# Sheet3.net
KiCad netlist of a schematic drawn in Altium Designer
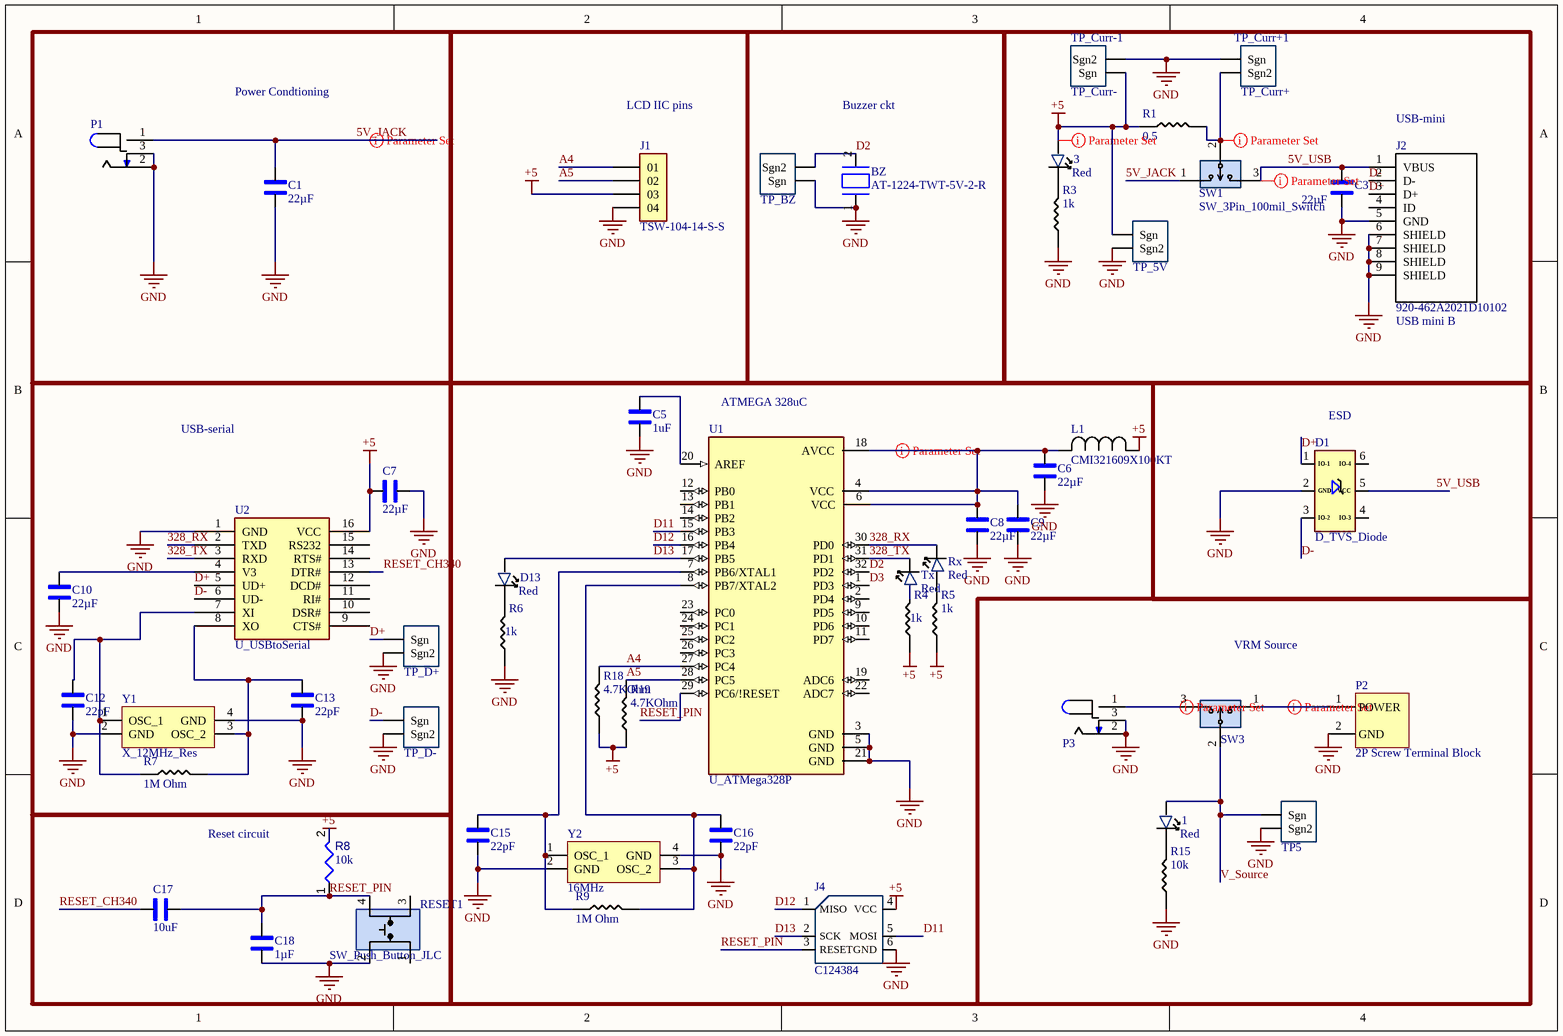
[diagram p0: Sheet3.SchDoc]

(export (version "E")
  (design (tool "Eeschema 10.0.6"))
  (components
    (comp (ref "1")
      (value "Red")
      (footprint "LED_1206")
      (description "Red 621~631nm 1206 Light Emitting Diodes (LED) RoHS")
      (fields (field (name "LCSC PART#") "C93133") (field (name "MFR PART #") "15-21/R6C-FQ1R1B/2T"))
      (libsource (lib "University of Colorado") (part "LED_YELLOW_1206"))
    )
    (comp (ref "3")
      (value "Red")
      (footprint "LED_1206")
      (description "Red 621~631nm 1206 Light Emitting Diodes (LED) RoHS")
      (fields (field (name "LCSC PART#") "C93133") (field (name "MFR PART #") "15-21/R6C-FQ1R1B/2T"))
      (libsource (lib "University of Colorado") (part "LED_YELLOW_1206"))
    )
    (comp (ref "BZ")
      (value "AT-1224-TWT-5V-2-R")
      (footprint "BUZZER- TH")
      (fields (field (name "MFR PART #") "AT-1224-TWT-5V-2-R"))
      (libsource (lib "ECEN5730Lib_2023_05_DS") (part "BUZZER_1"))
    )
    (comp (ref "C1")
      (value "22µF")
      (footprint "1206_Passive_Capacitor")
      (description "22uF ±10% 25V X5R 1206 Multilayer Ceramic Capacitors MLCC - SMD/SMT RoHS")
      (fields (field (name "LCSC PART#") "C12891") (field (name "MFR PART #") "CL31A226KAHNNNE"))
      (libsource (lib "University of Colorado") (part "C_47nF_1206"))
    )
    (comp (ref "C3")
      (value "22µF")
      (footprint "1206_Passive_Capacitor")
      (description "22uF ±10% 25V X5R 1206 Multilayer Ceramic Capacitors MLCC - SMD/SMT RoHS")
      (fields (field (name "LCSC PART#") "C12891") (field (name "MFR PART #") "CL31A226KAHNNNE"))
      (libsource (lib "University of Colorado") (part "C_47nF_1206"))
    )
    (comp (ref "C5")
      (value "1uF")
      (footprint "1206_Passive_Capacitor")
      (description "MULTILAYER CERAMIC CAPACITORS MLCC - SMD/SMT 1UF 50V 1206 ROHS")
      (fields (field (name "MFR PART #") "CL31B105KBHNNNE") (field (name "LCSC PART#") "C1848"))
      (libsource (lib "ECEN5730Lib_2023_05_DS") (part "C_1uF_1206"))
    )
    (comp (ref "C6")
      (value "22µF")
      (footprint "1206_Passive_Capacitor")
      (description "22uF ±10% 25V X5R 1206 Multilayer Ceramic Capacitors MLCC - SMD/SMT RoHS")
      (fields (field (name "LCSC PART#") "C12891") (field (name "MFR PART #") "CL31A226KAHNNNE"))
      (libsource (lib "University of Colorado") (part "C_47nF_1206"))
    )
    (comp (ref "C7")
      (value "22µF")
      (footprint "1206_Passive_Capacitor")
      (description "22uF ±10% 25V X5R 1206 Multilayer Ceramic Capacitors MLCC - SMD/SMT RoHS")
      (fields (field (name "LCSC PART#") "C12891") (field (name "MFR PART #") "CL31A226KAHNNNE"))
      (libsource (lib "University of Colorado") (part "C_47nF_1206"))
    )
    (comp (ref "C8")
      (value "22µF")
      (footprint "1206_Passive_Capacitor")
      (description "22uF ±10% 25V X5R 1206 Multilayer Ceramic Capacitors MLCC - SMD/SMT RoHS")
      (fields (field (name "LCSC PART#") "C12891") (field (name "MFR PART #") "CL31A226KAHNNNE"))
      (libsource (lib "University of Colorado") (part "C_47nF_1206"))
    )
    (comp (ref "C9")
      (value "22µF")
      (footprint "1206_Passive_Capacitor")
      (description "22uF ±10% 25V X5R 1206 Multilayer Ceramic Capacitors MLCC - SMD/SMT RoHS")
      (fields (field (name "LCSC PART#") "C12891") (field (name "MFR PART #") "CL31A226KAHNNNE"))
      (libsource (lib "University of Colorado") (part "C_47nF_1206"))
    )
    (comp (ref "C10")
      (value "22µF")
      (footprint "1206_Passive_Capacitor")
      (description "22uF ±10% 25V X5R 1206 Multilayer Ceramic Capacitors MLCC - SMD/SMT RoHS")
      (fields (field (name "LCSC PART#") "C12891") (field (name "MFR PART #") "CL31A226KAHNNNE"))
      (libsource (lib "University of Colorado") (part "C_47nF_1206"))
    )
    (comp (ref "C12")
      (value "22pF")
      (footprint "1206_Passive_Capacitor")
      (description "22uF ±10% 25V X5R 1206 Multilayer Ceramic Capacitors MLCC - SMD/SMT RoHS")
      (fields (field (name "LCSC PART#") "C12891") (field (name "MFR PART #") "CL31A226KAHNNNE"))
      (libsource (lib "University of Colorado") (part "C_47nF_1206"))
    )
    (comp (ref "C13")
      (value "22pF")
      (footprint "1206_Passive_Capacitor")
      (description "22uF ±10% 25V X5R 1206 Multilayer Ceramic Capacitors MLCC - SMD/SMT RoHS")
      (fields (field (name "LCSC PART#") "C12891") (field (name "MFR PART #") "CL31A226KAHNNNE"))
      (libsource (lib "University of Colorado") (part "C_47nF_1206"))
    )
    (comp (ref "C15")
      (value "22pF")
      (footprint "1206_Passive_Capacitor")
      (description "22uF ±10% 25V X5R 1206 Multilayer Ceramic Capacitors MLCC - SMD/SMT RoHS")
      (fields (field (name "LCSC PART#") "C12891") (field (name "MFR PART #") "CL31A226KAHNNNE"))
      (libsource (lib "University of Colorado") (part "C_47nF_1206"))
    )
    (comp (ref "C16")
      (value "22pF")
      (footprint "1206_Passive_Capacitor")
      (description "22uF ±10% 25V X5R 1206 Multilayer Ceramic Capacitors MLCC - SMD/SMT RoHS")
      (fields (field (name "LCSC PART#") "C12891") (field (name "MFR PART #") "CL31A226KAHNNNE"))
      (libsource (lib "University of Colorado") (part "C_47nF_1206"))
    )
    (comp (ref "C17")
      (value "10uF")
      (footprint "1206_Passive_Capacitor")
      (description "10uF ±10% 50V X5R 1206 Multilayer Ceramic Capacitors MLCC - SMD/SMT RoHS")
      (fields (field (name "LCSC PART#") "C13585") (field (name "MFR PART #") "CL31A106KBHNNNE"))
      (libsource (lib "ECEN5730Lib_2023_05_DS") (part "C_10uF_1206"))
    )
    (comp (ref "C18")
      (value "1µF")
      (footprint "1206_Passive_Capacitor")
      (description "MULTILAYER CERAMIC CAPACITORS MLCC - SMD/SMT 1UF 50V 1206 ROHS")
      (fields (field (name "MFR PART #") "CL31B105KBHNNNE") (field (name "LCSC PART#") "C1848"))
      (libsource (lib "University of Colorado") (part "C_47nF_1206"))
    )
    (comp (ref "D1")
      (value "D_TVS_Diode")
      (footprint "TVS")
      (description "TVS SOT-23-6 ROHS")
      (fields (field (name "LCSC PART#") "C85364") (field (name "MFR PART #") "SRV05-4-P-T7"))
      (libsource (lib "University of Colorado") (part "D_TVS_Diode"))
    )
    (comp (ref "D13")
      (value "Red")
      (footprint "LED_1206")
      (description "Red 621~631nm 1206 Light Emitting Diodes (LED) RoHS")
      (fields (field (name "LCSC PART#") "C93133") (field (name "MFR PART #") "15-21/R6C-FQ1R1B/2T"))
      (libsource (lib "University of Colorado") (part "LED_YELLOW_1206"))
    )
    (comp (ref "J1")
      (value "TSW-104-14-S-S")
      (footprint "JM-4_TSW-104-14-S-S")
      (description "Square Pins 2.5mm 6mm -40℃~+105℃ 1 4 3mm 2.54mm Black 1x4P Straight,P=2.54mm  Pin Headers ROHS")
      (fields (field (name "MFR PART #") "PZ254V-11-04P") (field (name "LCSC PART#") "C2691448"))
      (libsource (lib "ECEN5730Lib_2023_05_DS") (part "JM_4_PIN_MALE"))
    )
    (comp (ref "J2")
      (value "USB mini B")
      (footprint "USB_MINI_B")
      (description "Through Hole USB Connectors RoHS")
      (fields
        (field (name "LCSC PART#") "C46398")
        (field (name "MFR PART #") "920-462A2021D10102")
        (field (name "Comment") "J_USB_B_Mini")
      )
      (libsource (lib "University of Colorado") (part "J_USB_B_Mini"))
    )
    (comp (ref "J4")
      (value "NRPN032PAEN-RC")
      (footprint "ICSP")
      (description "Connector Header Through Hole 6 position 0.079\" (2.00mm)")
      (fields (field (name "LCSC PART#") "C124384"))
      (libsource (lib "ECEN5730Lib_2023_05_DS") (part "J_ICSP"))
    )
    (comp (ref "L1")
      (value "FB_10uH_1206")
      (footprint "AIML-1206_ABR-M")
      (description "25mA 10uH ±10% 800mO 1206  Inductors (SMD) ROHS")
      (fields (field (name "LCSC PART#") "C1051") (field (name "MFR PART #") "CMI321609X100KT"))
      (libsource (lib "University of Colorado") (part "FB_10uH_1206"))
    )
    (comp (ref "P1")
      (value "P_Power Jack")
      (footprint "Power_Jack")
      (description "Power Barrel Connector Jack 2.10mm ID (0.083\"), 5.50mm OD (0.217\") Through Hole, Right Angle")
      (fields (field (name "LCSC PART#") "C136744") (field (name "MFR PART #") "PJ-102A"))
      (libsource (lib "University of Colorado") (part "P_Power Jack"))
    )
    (comp (ref "P2")
      (value "2P Screw Terminal Block")
      (footprint "P_Terminal block 3.5mm-pitch")
      (description "Green Straight pin 3.5mm  pitch; P=3.5mm  Screw terminal ROHS")
      (fields (field (name "MFR PART #") "KF350-3.5-2P") (field (name "MANUFACTURER") "Cixi Kefa Elec"))
      (libsource (lib "ECEN5730Lib_2023_05_DS") (part "P_Terminal block"))
    )
    (comp (ref "P3")
      (value "Power Jack")
      (footprint "Power_Jack")
      (description "Power Barrel Connector Jack 2.10mm ID (0.083\"), 5.50mm OD (0.217\") Through Hole, Right Angle")
      (fields (field (name "MFR PART #") "PJ-102A") (field (name "LCSC PART#") "C136744"))
      (libsource (lib "ECEN5730Lib_2023_05_DS") (part "P_Power Jack"))
    )
    (comp (ref "R1")
      (value "0.5")
      (footprint "1206_Passive_Resitor")
      (description "Resistors/Shunt 250mW 500mO ±800ppm/? ±5% 1206  Current Sense  Resistors ROHS")
      (fields (field (name "MFR PART #") "1206W4J050KT5E") (field (name "LCSC PART#") "C247433"))
      (libsource (lib "University of Colorado") (part "R_500mOhm_1206"))
    )
    (comp (ref "R3")
      (value "1k")
      (footprint "1206_Passive_Resitor")
      (description "CHIP RESISTOR - SURFACE MOUNT 1KOHMS ±1% 1/4W 1206 ROHS")
      (fields (field (name "LCSC PART#") "C4410") (field (name "MFR PART #") "RNCP1206FTD1K00CT"))
      (libsource (lib "University of Colorado") (part "R_500mOhm_1206"))
    )
    (comp (ref "R4")
      (value "1k")
      (footprint "1206_Passive_Resitor")
      (description "CHIP RESISTOR - SURFACE MOUNT 1KOHMS ±1% 1/4W 1206 ROHS")
      (fields (field (name "LCSC PART#") "C4410") (field (name "MFR PART #") "RNCP1206FTD1K00CT"))
      (libsource (lib "University of Colorado") (part "R_500mOhm_1206"))
    )
    (comp (ref "R5")
      (value "1k")
      (footprint "1206_Passive_Resitor")
      (description "CHIP RESISTOR - SURFACE MOUNT 1KOHMS ±1% 1/4W 1206 ROHS")
      (fields (field (name "LCSC PART#") "C4410") (field (name "MFR PART #") "RNCP1206FTD1K00CT"))
      (libsource (lib "University of Colorado") (part "R_500mOhm_1206"))
    )
    (comp (ref "R6")
      (value "1k")
      (footprint "1206_Passive_Resitor")
      (description "CHIP RESISTOR - SURFACE MOUNT 1KOHMS ±1% 1/4W 1206 ROHS")
      (fields (field (name "LCSC PART#") "C4410") (field (name "MFR PART #") "RNCP1206FTD1K00CT"))
      (libsource (lib "University of Colorado") (part "R_500mOhm_1206"))
    )
    (comp (ref "R7")
      (value "1M Ohm")
      (footprint "1206_Passive_Resitor")
      (description "CHIP RESISTOR - SURFACE MOUNT 1MOHMS ±1% 1/4W 1206 ROHS")
      (fields (field (name "MFR PART #") "RMCF1206JT1M00") (field (name "LCSC PART#") "C17927"))
      (libsource (lib "ECEN5730Lib_2023_05_DS") (part "R_1M_1206"))
    )
    (comp (ref "R8")
      (value "10k")
      (footprint "RESC3216X60X45ML15T20")
      (description "Chip Resistor, 10 KOhm, +/- 1%, 0.25 W, -55 to 155 degC, 1206 (3216 Metric)")
      (fields (field (name "TOLERANCE") "1%") (field (name "POWER") "250mW"))
      (libsource (lib "University of Colorado") (part "RES-2"))
    )
    (comp (ref "R9")
      (value "1M Ohm")
      (footprint "1206_Passive_Resitor")
      (description "CHIP RESISTOR - SURFACE MOUNT 1MOHMS ±1% 1/4W 1206 ROHS")
      (fields (field (name "MFR PART #") "RMCF1206JT1M00") (field (name "LCSC PART#") "C17927"))
      (libsource (lib "ECEN5730Lib_2023_05_DS") (part "R_1M_1206"))
    )
    (comp (ref "R15")
      (value "10k")
      (footprint "1206_Passive_Resitor")
      (description "CHIP RESISTOR - SURFACE MOUNT 1KOHMS ±1% 1/4W 1206 ROHS")
      (fields (field (name "LCSC PART#") "C4410") (field (name "MFR PART #") "RNCP1206FTD1K00CT"))
      (libsource (lib "University of Colorado") (part "R_500mOhm_1206"))
    )
    (comp (ref "R18")
      (value "4.7KOhm")
      (footprint "1206_Passive_Resitor")
      (description "4.7kΩ ±1% 0.25W ±100ppm/℃ 1206 Chip Resistor - Surface Mount RoHS")
      (fields (field (name "LCSC PART#") "C17936") (field (name "MFR PART #") "1206W4F4701T5E"))
      (libsource (lib "ECEN5730Lib_2023_05_DS") (part "R_4.7k_1206"))
    )
    (comp (ref "R19")
      (value "4.7KOhm")
      (footprint "1206_Passive_Resitor")
      (description "4.7kΩ ±1% 0.25W ±100ppm/℃ 1206 Chip Resistor - Surface Mount RoHS")
      (fields (field (name "LCSC PART#") "C17936") (field (name "MFR PART #") "1206W4F4701T5E"))
      (libsource (lib "ECEN5730Lib_2023_05_DS") (part "R_4.7k_1206"))
    )
    (comp (ref "RESET1")
      (value "SW_Push_Button_JLC")
      (footprint "Switch_JLC")
      (description "Tactile Switch SPST-NO Top Actuated Surface Mount")
      (fields (field (name "MFR PART #") "KH-4.5X4.5X4.3H-STM") (field (name "LCSC PART#") "C2837550"))
      (libsource (lib "University of Colorado") (part "SW_Push_Button_JLC"))
    )
    (comp (ref "Rx")
      (value "Red")
      (footprint "LED_1206")
      (description "Red 621~631nm 1206 Light Emitting Diodes (LED) RoHS")
      (fields (field (name "LCSC PART#") "C93133") (field (name "MFR PART #") "15-21/R6C-FQ1R1B/2T"))
      (libsource (lib "University of Colorado") (part "LED_YELLOW_1206"))
    )
    (comp (ref "SW1")
      (value "SW_3Pin_100mil_Switch")
      (footprint "3_PIN_100mil")
      (description "Connector Header Through Hole 3 position 0.100\" (2.54mm)")
      (fields (field (name "LCSC PART#") "C49257") (field (name "MFR PART #") "PREC003SAAN-RC"))
      (libsource (lib "University of Colorado") (part "SW_3Pin_100mil_Switch"))
    )
    (comp (ref "SW3")
      (value "SW_3Pin_100mil_Switch")
      (footprint "3_PIN_100mil")
      (description "Connector Header Through Hole 3 position 0.100\" (2.54mm)")
      (fields (field (name "LCSC PART#") "C49257") (field (name "MFR PART #") "PREC003SAAN-RC"))
      (libsource (lib "") (part "SW_3Pin_100mil_Switch_1"))
    )
    (comp (ref "TP5")
      (value "10x Probe TP")
      (footprint "TP_Diff_Probe")
      (description "Test Point 300 mil centers")
      (libsource (lib "ECEN5730Lib_2023_05_DS") (part "TP_Diff_Probe"))
    )
    (comp (ref "TP_5V")
      (value "10x Probe TP")
      (footprint "TP_Diff_Probe")
      (description "Test Point 300 mil centers")
      (libsource (lib "ECEN5730Lib_2023_05_DS") (part "TP_Diff_Probe"))
    )
    (comp (ref "TP_BZ")
      (value "10x Probe TP")
      (footprint "TP_Diff_Probe")
      (description "Test Point 300 mil centers")
      (libsource (lib "") (part "TP_Diff_Probe_1"))
    )
    (comp (ref "TP_Curr+1")
      (value "TP_Curr+")
      (footprint "TP_Diff_Probe")
      (description "Test Point 300 mil centers")
      (libsource (lib "University of Colorado") (part "TP_Diff_Probe"))
    )
    (comp (ref "TP_Curr-1")
      (value "TP_Curr-")
      (footprint "TP_Diff_Probe")
      (description "Test Point 300 mil centers")
      (libsource (lib "") (part "TP_Diff_Probe_1"))
    )
    (comp (ref "TP_D+")
      (value "10x Probe TP")
      (footprint "TP_Diff_Probe")
      (description "Test Point 300 mil centers")
      (libsource (lib "ECEN5730Lib_2023_05_DS") (part "TP_Diff_Probe"))
    )
    (comp (ref "TP_D-")
      (value "10x Probe TP")
      (footprint "TP_Diff_Probe")
      (description "Test Point 300 mil centers")
      (libsource (lib "ECEN5730Lib_2023_05_DS") (part "TP_Diff_Probe"))
    )
    (comp (ref "Tx")
      (value "Red")
      (footprint "LED_1206")
      (description "Red 621~631nm 1206 Light Emitting Diodes (LED) RoHS")
      (fields (field (name "LCSC PART#") "C93133") (field (name "MFR PART #") "15-21/R6C-FQ1R1B/2T"))
      (libsource (lib "University of Colorado") (part "LED_YELLOW_1206"))
    )
    (comp (ref "U1")
      (value "U_ATMega328P")
      (footprint "ATMega328P")
      (description "AVR AVR® ATmega Microcontroller IC 8-Bit 20MHz 32KB (16K x 16) FLASH 32-TQFP (7x7)")
      (fields (field (name "MFR PART #") "ATMEGA328P-AU") (field (name "LCSC PART#") "C14877"))
      (libsource (lib "University of Colorado") (part "U_ATMega328P"))
    )
    (comp (ref "U2")
      (value "U_USBtoSerial")
      (footprint "USB to serial")
      (description "Transceiver USB 2.0 2Mbps SOP-16_150mil USB ICs RoHS")
      (fields (field (name "LCSC PART#") "C14267") (field (name "MFR PART #") "CH340G"))
      (libsource (lib "University of Colorado") (part "U_USBtoSerial"))
    )
    (comp (ref "Y1")
      (value "X_12MHz_Res")
      (footprint "Crystal resonator")
      (description "SMD Crystal Resonators 12MHz ±10ppm SMD-3225_4P RoHS")
      (fields (field (name "MFR PART #") "X322512MSB4SI") (field (name "LCSC PART#") "C9002"))
      (libsource (lib "University of Colorado") (part "X_12MHz_Res"))
    )
    (comp (ref "Y2")
      (value "16MHz")
      (footprint "Crystal resonator")
      (description "±10ppm 16000000Hz -40℃~85℃ 贴片无源晶振 60Ω 9pF SMD3225-4P Crystals ROHS")
      (fields (field (name "LCSC PART#") "C13738") (field (name "MFR PART #") "X322516MLB4SI"))
      (libsource (lib "ECEN5730Lib_2023_05_DS") (part "X_16Mhz_Res"))
    )
  )
  (nets
    (net (code "1") (name "+5") (class "Default")
      (node (ref "3") (pin "1") (pinfunction "1_1") (pintype "passive"))
      (node (ref "C7") (pin "1") (pinfunction "1_1") (pintype "passive"))
      (node (ref "J1") (pin "03") (pinfunction "03_03") (pintype "passive"))
      (node (ref "J4") (pin "4") (pinfunction "VCC_4") (pintype "passive"))
      (node (ref "L1") (pin "1") (pinfunction "1_1") (pintype "passive"))
      (node (ref "R1") (pin "1") (pinfunction "1_1") (pintype "passive"))
      (node (ref "R18") (pin "1") (pinfunction "1_1") (pintype "passive"))
      (node (ref "R19") (pin "1") (pinfunction "1_1") (pintype "passive"))
      (node (ref "R4") (pin "1") (pinfunction "1_1") (pintype "passive"))
      (node (ref "R5") (pin "1") (pinfunction "1_1") (pintype "passive"))
      (node (ref "R8") (pin "2") (pinfunction "2_2") (pintype "passive"))
      (node (ref "TP_5V") (pin "1") (pinfunction "Sgn_1") (pintype "passive"))
      (node (ref "TP_Curr-1") (pin "1") (pinfunction "Sgn_1") (pintype "passive"))
      (node (ref "U2") (pin "16") (pinfunction "VCC_16") (pintype "passive"))
    )
    (net (code "2") (name "/5V_JACK") (class "Default")
      (node (ref "C1") (pin "2") (pinfunction "2_2") (pintype "passive"))
      (node (ref "P1") (pin "1") (pinfunction "1_1") (pintype "power_in"))
      (node (ref "SW1") (pin "1") (pinfunction "1_1") (pintype "passive"))
    )
    (net (code "3") (name "/5V_USB") (class "Default")
      (node (ref "C3") (pin "2") (pinfunction "2_2") (pintype "passive"))
      (node (ref "D1") (pin "5") (pinfunction "VCC_5") (pintype "passive"))
      (node (ref "J2") (pin "1") (pinfunction "VBUS_1") (pintype "passive"))
      (node (ref "SW1") (pin "3") (pinfunction "3_3") (pintype "passive"))
    )
    (net (code "4") (name "/328_RX") (class "Default")
      (node (ref "Rx") (pin "2") (pinfunction "2_2") (pintype "passive"))
      (node (ref "U1") (pin "30") (pinfunction "PD0_30") (pintype "bidirectional"))
      (node (ref "U2") (pin "2") (pinfunction "TXD_2") (pintype "passive"))
    )
    (net (code "5") (name "/328_TX") (class "Default")
      (node (ref "Tx") (pin "2") (pinfunction "2_2") (pintype "passive"))
      (node (ref "U1") (pin "31") (pinfunction "PD1_31") (pintype "bidirectional"))
      (node (ref "U2") (pin "3") (pinfunction "RXD_3") (pintype "passive"))
    )
    (net (code "6") (name "/A4") (class "Default")
      (node (ref "J1") (pin "01") (pinfunction "01_01") (pintype "passive"))
      (node (ref "R18") (pin "2") (pinfunction "2_2") (pintype "passive"))
      (node (ref "U1") (pin "27") (pinfunction "PC4_27") (pintype "bidirectional"))
    )
    (net (code "7") (name "/A5") (class "Default")
      (node (ref "J1") (pin "02") (pinfunction "02_02") (pintype "passive"))
      (node (ref "R19") (pin "2") (pinfunction "2_2") (pintype "passive"))
      (node (ref "U1") (pin "28") (pinfunction "PC5_28") (pintype "bidirectional"))
    )
    (net (code "8") (name "/D+") (class "Default")
      (node (ref "D1") (pin "1") (pinfunction "IO-1_1") (pintype "passive"))
      (node (ref "J2") (pin "3") (pinfunction "D+_3") (pintype "passive"))
      (node (ref "TP_D+") (pin "1") (pinfunction "Sgn_1") (pintype "passive"))
      (node (ref "U2") (pin "5") (pinfunction "UD+_5") (pintype "passive"))
    )
    (net (code "9") (name "/D-") (class "Default")
      (node (ref "D1") (pin "3") (pinfunction "IO-2_3") (pintype "passive"))
      (node (ref "J2") (pin "2") (pinfunction "D-_2") (pintype "passive"))
      (node (ref "TP_D-") (pin "1") (pinfunction "Sgn_1") (pintype "passive"))
      (node (ref "U2") (pin "6") (pinfunction "UD-_6") (pintype "passive"))
    )
    (net (code "10") (name "/D2") (class "Default")
      (node (ref "BZ") (pin "2") (pinfunction "BZ2_2") (pintype "passive"))
      (node (ref "TP_BZ") (pin "2") (pinfunction "Sgn2_2") (pintype "passive"))
      (node (ref "U1") (pin "32") (pinfunction "PD2_32") (pintype "bidirectional"))
    )
    (net (code "11") (name "/D3") (class "Default")
      (node (ref "U1") (pin "1") (pinfunction "PD3_1") (pintype "bidirectional"))
    )
    (net (code "12") (name "/D11") (class "Default")
      (node (ref "J4") (pin "5") (pinfunction "MOSI_5") (pintype "passive"))
      (node (ref "U1") (pin "15") (pinfunction "PB3_15") (pintype "bidirectional"))
    )
    (net (code "13") (name "/D12") (class "Default")
      (node (ref "J4") (pin "1") (pinfunction "MISO_1") (pintype "passive"))
      (node (ref "U1") (pin "16") (pinfunction "PB4_16") (pintype "bidirectional"))
    )
    (net (code "14") (name "/D13") (class "Default")
      (node (ref "D13") (pin "1") (pinfunction "1_1") (pintype "passive"))
      (node (ref "J4") (pin "2") (pinfunction "SCK_2") (pintype "passive"))
      (node (ref "U1") (pin "17") (pinfunction "PB5_17") (pintype "bidirectional"))
    )
    (net (code "15") (name "/RESET_CH340") (class "Default")
      (node (ref "C17") (pin "1") (pinfunction "1_1") (pintype "passive"))
      (node (ref "U2") (pin "13") (pinfunction "DTR#_13") (pintype "passive"))
    )
    (net (code "16") (name "/RESET_PIN") (class "Default")
      (node (ref "C17") (pin "2") (pinfunction "2_2") (pintype "passive"))
      (node (ref "C18") (pin "2") (pinfunction "2_2") (pintype "passive"))
      (node (ref "J4") (pin "3") (pinfunction "RESET_3") (pintype "passive"))
      (node (ref "R8") (pin "1") (pinfunction "1_1") (pintype "passive"))
      (node (ref "RESET1") (pin "4") (pinfunction "4_4") (pintype "passive"))
      (node (ref "U1") (pin "29") (pinfunction "PC6/!RESET_29") (pintype "bidirectional"))
    )
    (net (code "17") (name "/V_Source") (class "Default")
      (node (ref "1") (pin "1") (pinfunction "1_1") (pintype "passive"))
      (node (ref "SW3") (pin "2") (pinfunction "2_2") (pintype "passive"))
      (node (ref "TP5") (pin "1") (pinfunction "Sgn_1") (pintype "passive"))
    )
    (net (code "18") (name "GND") (class "Default")
      (node (ref "BZ") (pin "1") (pinfunction "BZ1_1") (pintype "passive"))
      (node (ref "C1") (pin "1") (pinfunction "1_1") (pintype "passive"))
      (node (ref "C10") (pin "2") (pinfunction "2_2") (pintype "passive"))
      (node (ref "C12") (pin "1") (pinfunction "1_1") (pintype "passive"))
      (node (ref "C13") (pin "1") (pinfunction "1_1") (pintype "passive"))
      (node (ref "C15") (pin "1") (pinfunction "1_1") (pintype "passive"))
      (node (ref "C16") (pin "1") (pinfunction "1_1") (pintype "passive"))
      (node (ref "C18") (pin "1") (pinfunction "1_1") (pintype "passive"))
      (node (ref "C3") (pin "1") (pinfunction "1_1") (pintype "passive"))
      (node (ref "C5") (pin "2") (pinfunction "2_2") (pintype "passive"))
      (node (ref "C6") (pin "1") (pinfunction "1_1") (pintype "passive"))
      (node (ref "C7") (pin "2") (pinfunction "2_2") (pintype "passive"))
      (node (ref "C8") (pin "1") (pinfunction "1_1") (pintype "passive"))
      (node (ref "C9") (pin "1") (pinfunction "1_1") (pintype "passive"))
      (node (ref "D1") (pin "2") (pinfunction "GND_2") (pintype "passive"))
      (node (ref "J1") (pin "04") (pinfunction "04_04") (pintype "passive"))
      (node (ref "J2") (pin "5") (pinfunction "GND_5") (pintype "passive"))
      (node (ref "J2") (pin "6") (pinfunction "SHIELD_6") (pintype "passive"))
      (node (ref "J2") (pin "7") (pinfunction "SHIELD_7") (pintype "passive"))
      (node (ref "J2") (pin "8") (pinfunction "SHIELD_8") (pintype "passive"))
      (node (ref "J2") (pin "9") (pinfunction "SHIELD_9") (pintype "passive"))
      (node (ref "J4") (pin "6") (pinfunction "GND_6") (pintype "passive"))
      (node (ref "P1") (pin "2") (pinfunction "2_2") (pintype "power_in"))
      (node (ref "P1") (pin "3") (pinfunction "3_3") (pintype "power_in"))
      (node (ref "P2") (pin "2") (pinfunction "GND_2") (pintype "passive"))
      (node (ref "P3") (pin "2") (pinfunction "2_2") (pintype "power_in"))
      (node (ref "P3") (pin "3") (pinfunction "3_3") (pintype "power_in"))
      (node (ref "R15") (pin "1") (pinfunction "1_1") (pintype "passive"))
      (node (ref "R3") (pin "1") (pinfunction "1_1") (pintype "passive"))
      (node (ref "R6") (pin "1") (pinfunction "1_1") (pintype "passive"))
      (node (ref "RESET1") (pin "2") (pinfunction "2_2") (pintype "passive"))
      (node (ref "TP5") (pin "2") (pinfunction "Sgn2_2") (pintype "passive"))
      (node (ref "TP_5V") (pin "2") (pinfunction "Sgn2_2") (pintype "passive"))
      (node (ref "TP_BZ") (pin "1") (pinfunction "Sgn_1") (pintype "passive"))
      (node (ref "TP_Curr+1") (pin "1") (pinfunction "Sgn_1") (pintype "passive"))
      (node (ref "TP_Curr-1") (pin "2") (pinfunction "Sgn2_2") (pintype "passive"))
      (node (ref "TP_D+") (pin "2") (pinfunction "Sgn2_2") (pintype "passive"))
      (node (ref "TP_D-") (pin "2") (pinfunction "Sgn2_2") (pintype "passive"))
      (node (ref "U1") (pin "21") (pinfunction "GND_21") (pintype "power_in"))
      (node (ref "U1") (pin "3") (pinfunction "GND_3") (pintype "power_in"))
      (node (ref "U1") (pin "5") (pinfunction "GND_5") (pintype "power_in"))
      (node (ref "U2") (pin "1") (pinfunction "GND_1") (pintype "passive"))
      (node (ref "Y1") (pin "2") (pinfunction "GND_2") (pintype "passive"))
      (node (ref "Y1") (pin "4") (pinfunction "GND_4") (pintype "passive"))
      (node (ref "Y2") (pin "2") (pinfunction "GND_2") (pintype "passive"))
      (node (ref "Y2") (pin "4") (pinfunction "GND_4") (pintype "passive"))
    )
    (net (code "19") (name "Net-(1-Pad2)") (class "Default")
      (node (ref "1") (pin "2") (pinfunction "2_2") (pintype "passive"))
      (node (ref "R15") (pin "2") (pinfunction "2_2") (pintype "passive"))
    )
    (net (code "20") (name "Net-(3-Pad2)") (class "Default")
      (node (ref "3") (pin "2") (pinfunction "2_2") (pintype "passive"))
      (node (ref "R3") (pin "2") (pinfunction "2_2") (pintype "passive"))
    )
    (net (code "21") (name "Net-(D13-Pad2)") (class "Default")
      (node (ref "D13") (pin "2") (pinfunction "2_2") (pintype "passive"))
      (node (ref "R6") (pin "2") (pinfunction "2_2") (pintype "passive"))
    )
    (net (code "22") (name "Net-(P2-POWER)") (class "Default")
      (node (ref "P2") (pin "1") (pinfunction "POWER_1") (pintype "passive"))
      (node (ref "SW3") (pin "1") (pinfunction "1_1") (pintype "passive"))
    )
    (net (code "23") (name "Net-(P3-Pad1)") (class "Default")
      (node (ref "P3") (pin "1") (pinfunction "1_1") (pintype "power_in"))
      (node (ref "SW3") (pin "3") (pinfunction "3_3") (pintype "passive"))
    )
    (net (code "24") (name "Net-(R4-Pad2)") (class "Default")
      (node (ref "R4") (pin "2") (pinfunction "2_2") (pintype "passive"))
      (node (ref "Tx") (pin "1") (pinfunction "1_1") (pintype "passive"))
    )
    (net (code "25") (name "Net-(R5-Pad2)") (class "Default")
      (node (ref "R5") (pin "2") (pinfunction "2_2") (pintype "passive"))
      (node (ref "Rx") (pin "1") (pinfunction "1_1") (pintype "passive"))
    )
    (net (code "26") (name "Net-(TP_Curr+1-Sgn2)") (class "Default")
      (node (ref "R1") (pin "2") (pinfunction "2_2") (pintype "passive"))
      (node (ref "SW1") (pin "2") (pinfunction "2_2") (pintype "passive"))
      (node (ref "TP_Curr+1") (pin "2") (pinfunction "Sgn2_2") (pintype "passive"))
    )
    (net (code "27") (name "Net-(U1-AREF)") (class "Default")
      (node (ref "C5") (pin "1") (pinfunction "1_1") (pintype "passive"))
      (node (ref "U1") (pin "20") (pinfunction "AREF_20") (pintype "input"))
    )
    (net (code "28") (name "Net-(U1-AVCC)") (class "Default")
      (node (ref "C6") (pin "2") (pinfunction "2_2") (pintype "passive"))
      (node (ref "C8") (pin "2") (pinfunction "2_2") (pintype "passive"))
      (node (ref "C9") (pin "2") (pinfunction "2_2") (pintype "passive"))
      (node (ref "L1") (pin "2") (pinfunction "2_2") (pintype "passive"))
      (node (ref "U1") (pin "18") (pinfunction "AVCC_18") (pintype "power_in"))
      (node (ref "U1") (pin "4") (pinfunction "VCC_4") (pintype "power_in"))
      (node (ref "U1") (pin "6") (pinfunction "VCC_6") (pintype "power_in"))
    )
    (net (code "29") (name "Net-(U1-PB6{slash}XTAL1)") (class "Default")
      (node (ref "C15") (pin "2") (pinfunction "2_2") (pintype "passive"))
      (node (ref "R9") (pin "1") (pinfunction "1_1") (pintype "passive"))
      (node (ref "U1") (pin "7") (pinfunction "PB6/XTAL1_7") (pintype "bidirectional"))
      (node (ref "Y2") (pin "1") (pinfunction "OSC_1_1") (pintype "passive"))
    )
    (net (code "30") (name "Net-(U1-PB7{slash}XTAL2)") (class "Default")
      (node (ref "C16") (pin "2") (pinfunction "2_2") (pintype "passive"))
      (node (ref "R9") (pin "2") (pinfunction "2_2") (pintype "passive"))
      (node (ref "U1") (pin "8") (pinfunction "PB7/XTAL2_8") (pintype "bidirectional"))
      (node (ref "Y2") (pin "3") (pinfunction "OSC_2_3") (pintype "passive"))
    )
    (net (code "31") (name "Net-(U2-V3)") (class "Default")
      (node (ref "C10") (pin "1") (pinfunction "1_1") (pintype "passive"))
      (node (ref "U2") (pin "4") (pinfunction "V3_4") (pintype "passive"))
    )
    (net (code "32") (name "Net-(U2-XI)") (class "Default")
      (node (ref "C12") (pin "2") (pinfunction "2_2") (pintype "passive"))
      (node (ref "R7") (pin "1") (pinfunction "1_1") (pintype "passive"))
      (node (ref "U2") (pin "7") (pinfunction "XI_7") (pintype "passive"))
      (node (ref "Y1") (pin "1") (pinfunction "OSC_1_1") (pintype "passive"))
    )
    (net (code "33") (name "Net-(U2-XO)") (class "Default")
      (node (ref "C13") (pin "2") (pinfunction "2_2") (pintype "passive"))
      (node (ref "R7") (pin "2") (pinfunction "2_2") (pintype "passive"))
      (node (ref "U2") (pin "8") (pinfunction "XO_8") (pintype "passive"))
      (node (ref "Y1") (pin "3") (pinfunction "OSC_2_3") (pintype "passive"))
    )
    (net (code "34") (name "unconnected-(D1-IO-3-Pad4)") (class "Default")
      (node (ref "D1") (pin "4") (pinfunction "IO-3_4") (pintype "passive"))
    )
    (net (code "35") (name "unconnected-(D1-IO-4-Pad6)") (class "Default")
      (node (ref "D1") (pin "6") (pinfunction "IO-4_6") (pintype "passive"))
    )
    (net (code "36") (name "unconnected-(J2-ID-Pad4)") (class "Default")
      (node (ref "J2") (pin "4") (pinfunction "ID_4") (pintype "passive"))
    )
    (net (code "37") (name "unconnected-(RESET1-Pad1)") (class "Default")
      (node (ref "RESET1") (pin "1") (pinfunction "1_1") (pintype "passive"))
    )
    (net (code "38") (name "unconnected-(RESET1-Pad3)") (class "Default")
      (node (ref "RESET1") (pin "3") (pinfunction "3_3") (pintype "passive"))
    )
    (net (code "39") (name "unconnected-(U1-ADC6-Pad19)") (class "Default")
      (node (ref "U1") (pin "19") (pinfunction "ADC6_19") (pintype "bidirectional"))
    )
    (net (code "40") (name "unconnected-(U1-ADC7-Pad22)") (class "Default")
      (node (ref "U1") (pin "22") (pinfunction "ADC7_22") (pintype "bidirectional"))
    )
    (net (code "41") (name "unconnected-(U1-PB0-Pad12)") (class "Default")
      (node (ref "U1") (pin "12") (pinfunction "PB0_12") (pintype "bidirectional"))
    )
    (net (code "42") (name "unconnected-(U1-PB1-Pad13)") (class "Default")
      (node (ref "U1") (pin "13") (pinfunction "PB1_13") (pintype "bidirectional"))
    )
    (net (code "43") (name "unconnected-(U1-PB2-Pad14)") (class "Default")
      (node (ref "U1") (pin "14") (pinfunction "PB2_14") (pintype "bidirectional"))
    )
    (net (code "44") (name "unconnected-(U1-PC0-Pad23)") (class "Default")
      (node (ref "U1") (pin "23") (pinfunction "PC0_23") (pintype "bidirectional"))
    )
    (net (code "45") (name "unconnected-(U1-PC1-Pad24)") (class "Default")
      (node (ref "U1") (pin "24") (pinfunction "PC1_24") (pintype "bidirectional"))
    )
    (net (code "46") (name "unconnected-(U1-PC2-Pad25)") (class "Default")
      (node (ref "U1") (pin "25") (pinfunction "PC2_25") (pintype "bidirectional"))
    )
    (net (code "47") (name "unconnected-(U1-PC3-Pad26)") (class "Default")
      (node (ref "U1") (pin "26") (pinfunction "PC3_26") (pintype "bidirectional"))
    )
    (net (code "48") (name "unconnected-(U1-PD4-Pad2)") (class "Default")
      (node (ref "U1") (pin "2") (pinfunction "PD4_2") (pintype "bidirectional"))
    )
    (net (code "49") (name "unconnected-(U1-PD5-Pad9)") (class "Default")
      (node (ref "U1") (pin "9") (pinfunction "PD5_9") (pintype "bidirectional"))
    )
    (net (code "50") (name "unconnected-(U1-PD6-Pad10)") (class "Default")
      (node (ref "U1") (pin "10") (pinfunction "PD6_10") (pintype "bidirectional"))
    )
    (net (code "51") (name "unconnected-(U1-PD7-Pad11)") (class "Default")
      (node (ref "U1") (pin "11") (pinfunction "PD7_11") (pintype "bidirectional"))
    )
    (net (code "52") (name "unconnected-(U2-CTS#-Pad9)") (class "Default")
      (node (ref "U2") (pin "9") (pinfunction "CTS#_9") (pintype "passive"))
    )
    (net (code "53") (name "unconnected-(U2-DCD#-Pad12)") (class "Default")
      (node (ref "U2") (pin "12") (pinfunction "DCD#_12") (pintype "passive"))
    )
    (net (code "54") (name "unconnected-(U2-DSR#-Pad10)") (class "Default")
      (node (ref "U2") (pin "10") (pinfunction "DSR#_10") (pintype "passive"))
    )
    (net (code "55") (name "unconnected-(U2-RI#-Pad11)") (class "Default")
      (node (ref "U2") (pin "11") (pinfunction "RI#_11") (pintype "passive"))
    )
    (net (code "56") (name "unconnected-(U2-RS232-Pad15)") (class "Default")
      (node (ref "U2") (pin "15") (pinfunction "RS232_15") (pintype "passive"))
    )
    (net (code "57") (name "unconnected-(U2-RTS#-Pad14)") (class "Default")
      (node (ref "U2") (pin "14") (pinfunction "RTS#_14") (pintype "passive"))
    )
  )
)
